# AdaptSensor.net
KiCad netlist of a schematic drawn in EAGLE
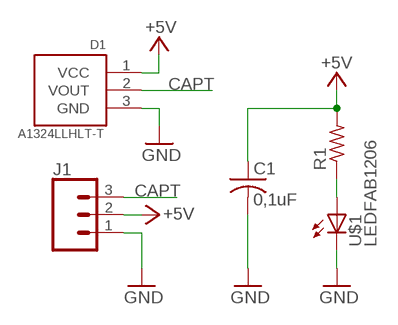
[diagram p0: schematic, sheet 1]

(export (version "E")
  (design (tool "Eeschema 10.0.6"))
  (components
    (comp (ref "C1")
      (value "0,1uF")
      (footprint "eagle-import:C1206FAB")
      (libsource (lib "eagle-import") (part "CAP-US1206FAB"))
    )
    (comp (ref "D1")
      (value "A1324LLHLT-T")
      (footprint "eagle-import:SOT190P290X100-3N")
      (fields (field (name "MF") "Allegro"))
      (libsource (lib "eagle-import") (part "A1324LLHLT-T"))
    )
    (comp (ref "J1")
      (value "CONN_03POLAR")
      (footprint "eagle-import:MOLEX-1X3")
      (libsource (lib "eagle-import") (part "CONN_03POLAR"))
    )
    (comp (ref "R1")
      (value "RES-US1206FAB")
      (footprint "eagle-import:R1206FAB")
      (libsource (lib "eagle-import") (part "RES-US1206FAB"))
    )
    (comp (ref "U$1")
      (value "LEDFAB1206")
      (footprint "eagle-import:LED1206FAB")
      (libsource (lib "eagle-import") (part "LEDFAB1206"))
    )
  )
  (nets
    (net (code "1") (name "+5V") (class "Default")
      (node (ref "C1") (pin "1") (pinfunction "1_1") (pintype "passive"))
      (node (ref "D1") (pin "1") (pinfunction "VCC_1") (pintype "power_in"))
      (node (ref "J1") (pin "2") (pinfunction "2_2") (pintype "passive"))
      (node (ref "R1") (pin "2") (pinfunction "2_2") (pintype "passive"))
    )
    (net (code "2") (name "/CAPT") (class "Default")
      (node (ref "D1") (pin "2") (pinfunction "VOUT_2") (pintype "output"))
      (node (ref "J1") (pin "3") (pinfunction "3_3") (pintype "passive"))
    )
    (net (code "3") (name "GND") (class "Default")
      (node (ref "C1") (pin "2") (pinfunction "2_2") (pintype "passive"))
      (node (ref "D1") (pin "3") (pinfunction "GND_3") (pintype "passive"))
      (node (ref "J1") (pin "1") (pinfunction "1_1") (pintype "passive"))
      (node (ref "U$1") (pin "2") (pinfunction "C_2") (pintype "passive"))
    )
    (net (code "4") (name "Net-(U$1-A)") (class "Default")
      (node (ref "R1") (pin "1") (pinfunction "1_1") (pintype "passive"))
      (node (ref "U$1") (pin "1") (pinfunction "A_1") (pintype "passive"))
    )
  )
)
